# 7segement4digits1badidea-feathershield-h.net
KiCad netlist of a schematic drawn in EAGLE
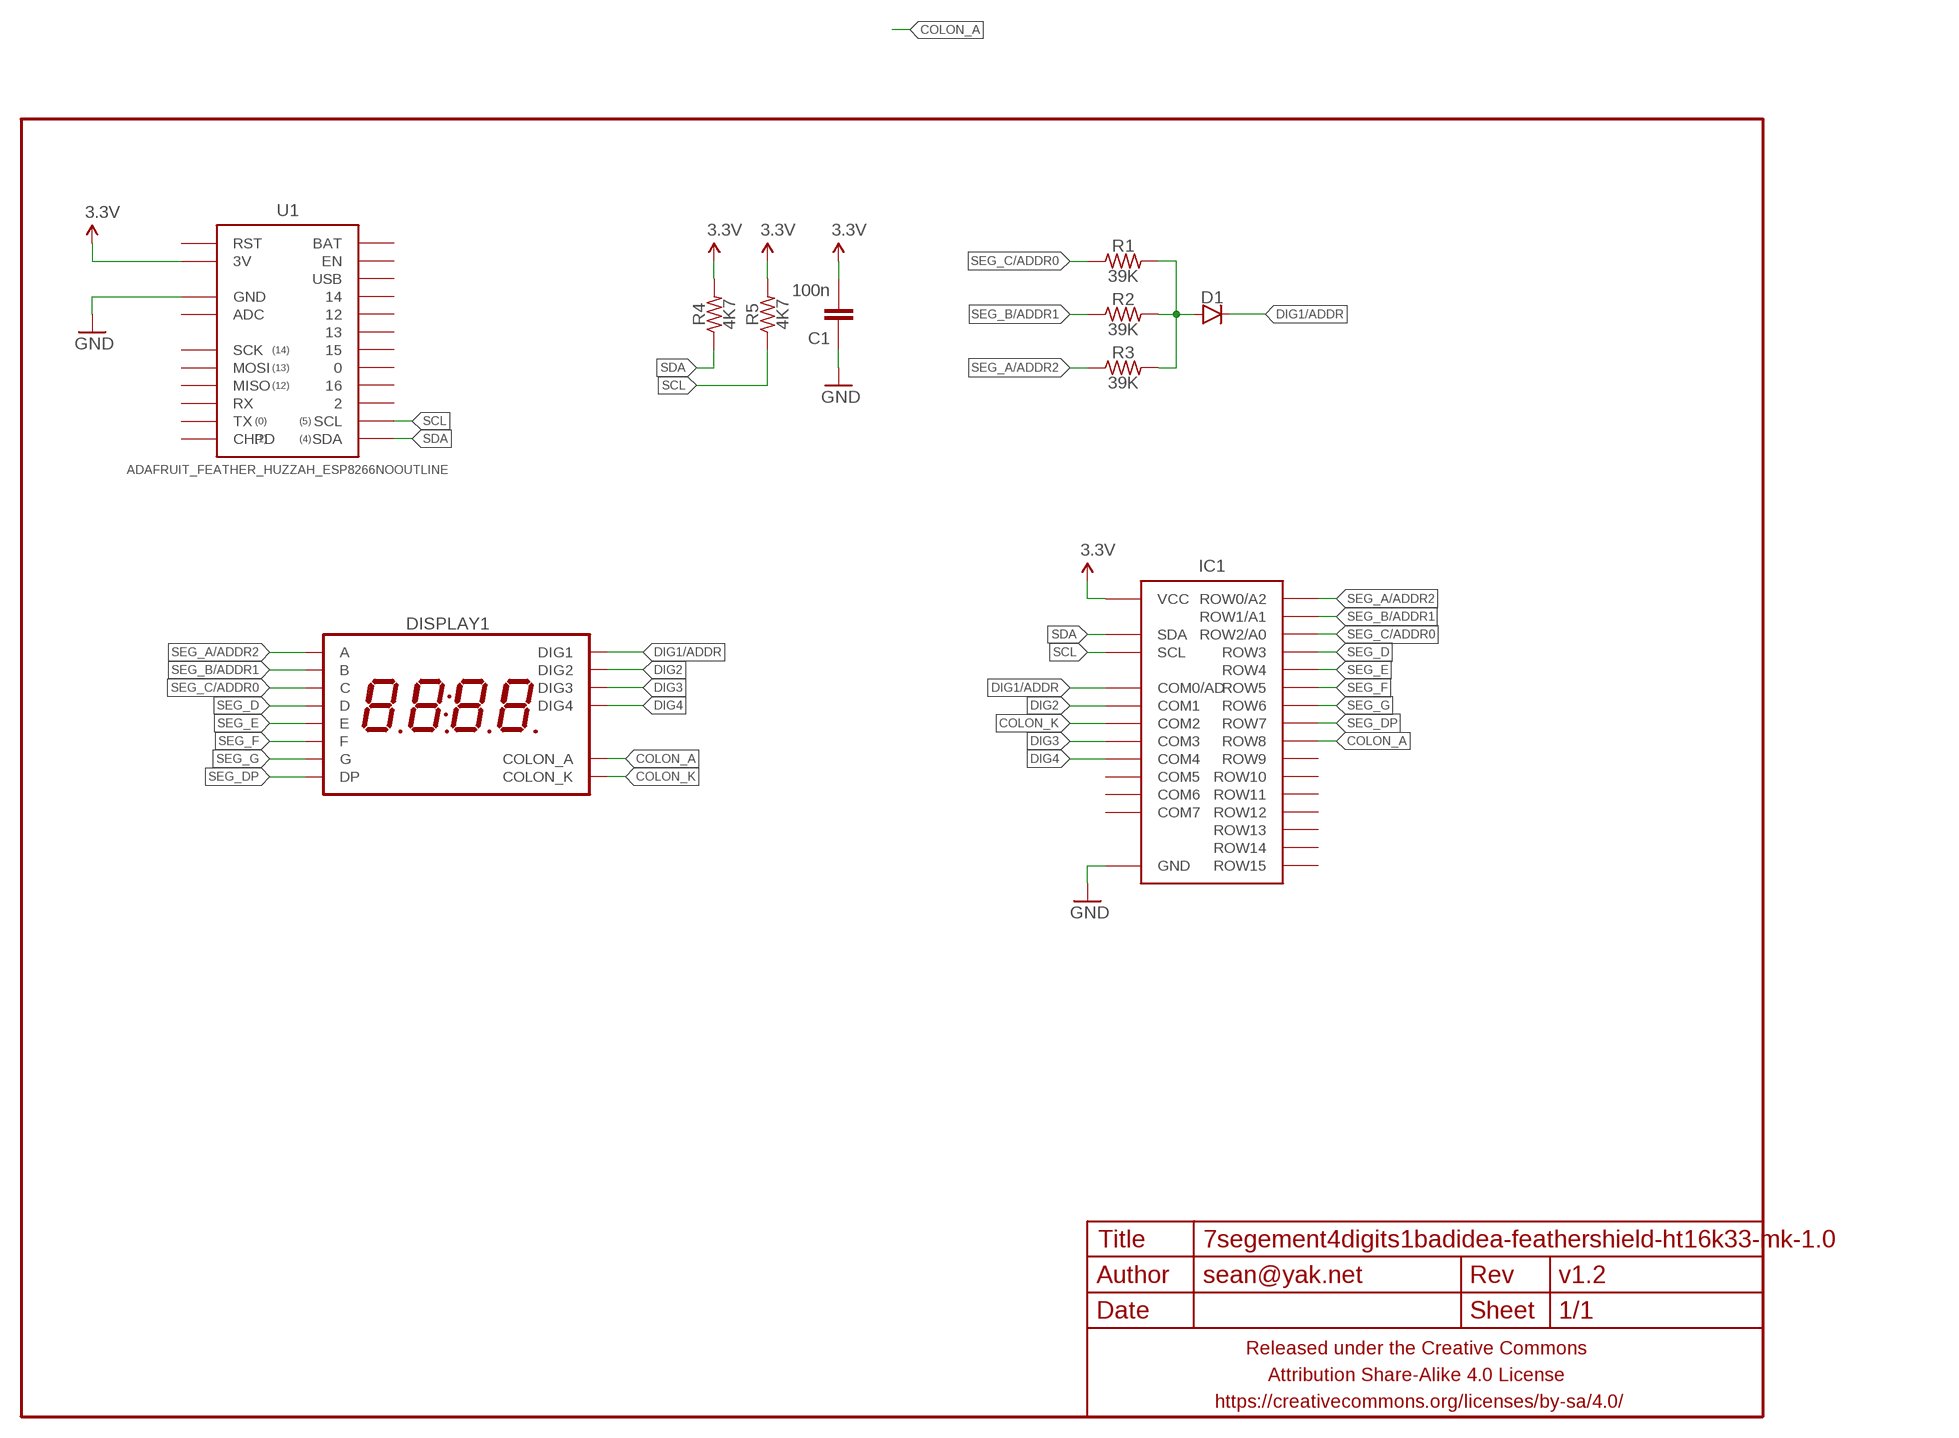
[diagram p0: schematic, sheet 1]

(export (version "E")
  (design (tool "Eeschema 10.0.6"))
  (components
    (comp (ref "C1")
      (value "100n")
      (footprint "eagle-import:C0603")
      (libsource (lib "eagle-import") (part "CAPACITOR-CERAMICC0603"))
    )
    (comp (ref "D1")
      (value "DIODESOD123")
      (footprint "eagle-import:SOD123")
      (libsource (lib "eagle-import") (part "DIODESOD123"))
    )
    (comp (ref "DISPLAY1")
      (value "7SEG_4DIGIT_COLON14.2MM-CC")
      (footprint "eagle-import:7SEG_4DIG_0.56IN_14MM_ADAFRUIT")
      (libsource (lib "eagle-import") (part "7SEG_4DIGIT_COLON14.2MM-CC"))
    )
    (comp (ref "FRAME1")
      (value "FRAME-LETTERNO_PACKAGE")
      (footprint "eagle-import:DUMMY")
      (fields (field (name "DESIGNER") "sean@yak.net") (field (name "VERSION") "v1.2"))
      (libsource (lib "eagle-import") (part "FRAME-LETTERNO_PACKAGE"))
    )
    (comp (ref "IC1")
      (value "HT16K33")
      (footprint "eagle-import:SOIC28W")
      (libsource (lib "eagle-import") (part "HT16K33-28SOIC28W"))
    )
    (comp (ref "R1")
      (value "39K")
      (footprint "eagle-import:R0603")
      (libsource (lib "eagle-import") (part "RESISTORR0603"))
    )
    (comp (ref "R2")
      (value "39K")
      (footprint "eagle-import:R0603")
      (libsource (lib "eagle-import") (part "RESISTORR0603"))
    )
    (comp (ref "R3")
      (value "39K")
      (footprint "eagle-import:R0603")
      (libsource (lib "eagle-import") (part "RESISTORR0603"))
    )
    (comp (ref "R4")
      (value "4K7")
      (footprint "eagle-import:R0603")
      (libsource (lib "eagle-import") (part "RESISTORR0603"))
    )
    (comp (ref "R5")
      (value "4K7")
      (footprint "eagle-import:R0603")
      (libsource (lib "eagle-import") (part "RESISTORR0603"))
    )
    (comp (ref "U1")
      (value "ADAFRUIT_FEATHER_HUZZAH_ESP8266NOOUTLINE")
      (footprint "eagle-import:ADAFRUIT_FEATHER_HUZZAH_NOOUTLINE")
      (libsource (lib "eagle-import") (part "ADAFRUIT_FEATHER_HUZZAH_ESP8266NOOUTLINE"))
    )
  )
  (nets
    (net (code "1") (name "3.3V") (class "Default")
      (node (ref "C1") (pin "2") (pinfunction "2_2") (pintype "passive"))
      (node (ref "IC1") (pin "28") (pinfunction "VCC_28") (pintype "bidirectional"))
      (node (ref "R4") (pin "2") (pinfunction "2_2") (pintype "passive"))
      (node (ref "R5") (pin "2") (pinfunction "2_2") (pintype "passive"))
      (node (ref "U1") (pin "3V") (pinfunction "3V_3V") (pintype "bidirectional"))
    )
    (net (code "2") (name "COLON_A") (class "Default")
      (node (ref "DISPLAY1") (pin "P$8") (pinfunction "COLON_A_P$8") (pintype "passive"))
      (node (ref "IC1") (pin "17") (pinfunction "ROW8_17") (pintype "bidirectional"))
    )
    (net (code "3") (name "COLON_K") (class "Default")
      (node (ref "DISPLAY1") (pin "P$7") (pinfunction "COLON_K_P$7") (pintype "passive"))
      (node (ref "IC1") (pin "4") (pinfunction "COM2_4") (pintype "bidirectional"))
    )
    (net (code "4") (name "DIG1{slash}ADDR") (class "Default")
      (node (ref "D1") (pin "C") (pinfunction "C_C") (pintype "passive"))
      (node (ref "DISPLAY1") (pin "P$14") (pinfunction "DIG1_P$14") (pintype "passive"))
      (node (ref "IC1") (pin "2") (pinfunction "COM0/AD_2") (pintype "bidirectional"))
    )
    (net (code "5") (name "DIG2") (class "Default")
      (node (ref "DISPLAY1") (pin "P$11") (pinfunction "DIG2_P$11") (pintype "passive"))
      (node (ref "IC1") (pin "3") (pinfunction "COM1_3") (pintype "bidirectional"))
    )
    (net (code "6") (name "DIG3") (class "Default")
      (node (ref "DISPLAY1") (pin "P$10") (pinfunction "DIG3_P$10") (pintype "passive"))
      (node (ref "IC1") (pin "5") (pinfunction "COM3_5") (pintype "bidirectional"))
    )
    (net (code "7") (name "DIG4") (class "Default")
      (node (ref "DISPLAY1") (pin "P$6") (pinfunction "DIG4_P$6") (pintype "passive"))
      (node (ref "IC1") (pin "6") (pinfunction "COM4_6") (pintype "bidirectional"))
    )
    (net (code "8") (name "GND") (class "Default")
      (node (ref "C1") (pin "1") (pinfunction "1_1") (pintype "passive"))
      (node (ref "IC1") (pin "1") (pinfunction "GND_1") (pintype "bidirectional"))
      (node (ref "U1") (pin "GND@0") (pinfunction "GND_GND@0") (pintype "bidirectional"))
    )
    (net (code "9") (name "Net-(D1-PadA)") (class "Default")
      (node (ref "D1") (pin "A") (pinfunction "A_A") (pintype "passive"))
      (node (ref "R1") (pin "2") (pinfunction "2_2") (pintype "passive"))
      (node (ref "R2") (pin "2") (pinfunction "2_2") (pintype "passive"))
      (node (ref "R3") (pin "2") (pinfunction "2_2") (pintype "passive"))
    )
    (net (code "10") (name "SCL") (class "Default")
      (node (ref "IC1") (pin "26") (pinfunction "SCL_26") (pintype "bidirectional"))
      (node (ref "R5") (pin "1") (pinfunction "1_1") (pintype "passive"))
      (node (ref "U1") (pin "SCL") (pinfunction "SCL_SCL") (pintype "bidirectional"))
    )
    (net (code "11") (name "SDA") (class "Default")
      (node (ref "IC1") (pin "27") (pinfunction "SDA_27") (pintype "bidirectional"))
      (node (ref "R4") (pin "1") (pinfunction "1_1") (pintype "passive"))
      (node (ref "U1") (pin "SDA") (pinfunction "SDA_SDA") (pintype "bidirectional"))
    )
    (net (code "12") (name "SEG_A{slash}ADDR2") (class "Default")
      (node (ref "DISPLAY1") (pin "P$13") (pinfunction "A_P$13") (pintype "passive"))
      (node (ref "IC1") (pin "25") (pinfunction "ROW0/A2_25") (pintype "bidirectional"))
      (node (ref "R3") (pin "1") (pinfunction "1_1") (pintype "passive"))
    )
    (net (code "13") (name "SEG_B{slash}ADDR1") (class "Default")
      (node (ref "DISPLAY1") (pin "P$9") (pinfunction "B_P$9") (pintype "passive"))
      (node (ref "IC1") (pin "24") (pinfunction "ROW1/A1_24") (pintype "bidirectional"))
      (node (ref "R2") (pin "1") (pinfunction "1_1") (pintype "passive"))
    )
    (net (code "14") (name "SEG_C{slash}ADDR0") (class "Default")
      (node (ref "DISPLAY1") (pin "P$4") (pinfunction "C_P$4") (pintype "passive"))
      (node (ref "IC1") (pin "23") (pinfunction "ROW2/A0_23") (pintype "bidirectional"))
      (node (ref "R1") (pin "1") (pinfunction "1_1") (pintype "passive"))
    )
    (net (code "15") (name "SEG_D") (class "Default")
      (node (ref "DISPLAY1") (pin "P$2") (pinfunction "D_P$2") (pintype "passive"))
      (node (ref "IC1") (pin "22") (pinfunction "ROW3_22") (pintype "bidirectional"))
    )
    (net (code "16") (name "SEG_DP") (class "Default")
      (node (ref "DISPLAY1") (pin "P$3") (pinfunction "DP_P$3") (pintype "passive"))
      (node (ref "IC1") (pin "18") (pinfunction "ROW7_18") (pintype "bidirectional"))
    )
    (net (code "17") (name "SEG_E") (class "Default")
      (node (ref "DISPLAY1") (pin "P$1") (pinfunction "E_P$1") (pintype "passive"))
      (node (ref "IC1") (pin "21") (pinfunction "ROW4_21") (pintype "bidirectional"))
    )
    (net (code "18") (name "SEG_F") (class "Default")
      (node (ref "DISPLAY1") (pin "P$12") (pinfunction "F_P$12") (pintype "passive"))
      (node (ref "IC1") (pin "20") (pinfunction "ROW5_20") (pintype "bidirectional"))
    )
    (net (code "19") (name "SEG_G") (class "Default")
      (node (ref "DISPLAY1") (pin "P$5") (pinfunction "G_P$5") (pintype "passive"))
      (node (ref "IC1") (pin "19") (pinfunction "ROW6_19") (pintype "bidirectional"))
    )
    (net (code "20") (name "unconnected-(IC1-COM5-Pad7)") (class "Default")
      (node (ref "IC1") (pin "7") (pinfunction "COM5_7") (pintype "bidirectional"))
    )
    (net (code "21") (name "unconnected-(IC1-COM6-Pad8)") (class "Default")
      (node (ref "IC1") (pin "8") (pinfunction "COM6_8") (pintype "bidirectional"))
    )
    (net (code "22") (name "unconnected-(IC1-COM7-Pad9)") (class "Default")
      (node (ref "IC1") (pin "9") (pinfunction "COM7_9") (pintype "bidirectional"))
    )
    (net (code "23") (name "unconnected-(IC1-ROW9-Pad16)") (class "Default")
      (node (ref "IC1") (pin "16") (pinfunction "ROW9_16") (pintype "bidirectional"))
    )
    (net (code "24") (name "unconnected-(IC1-ROW10-Pad15)") (class "Default")
      (node (ref "IC1") (pin "15") (pinfunction "ROW10_15") (pintype "bidirectional"))
    )
    (net (code "25") (name "unconnected-(IC1-ROW11-Pad14)") (class "Default")
      (node (ref "IC1") (pin "14") (pinfunction "ROW11_14") (pintype "bidirectional"))
    )
    (net (code "26") (name "unconnected-(IC1-ROW12-Pad13)") (class "Default")
      (node (ref "IC1") (pin "13") (pinfunction "ROW12_13") (pintype "bidirectional"))
    )
    (net (code "27") (name "unconnected-(IC1-ROW13-Pad12)") (class "Default")
      (node (ref "IC1") (pin "12") (pinfunction "ROW13_12") (pintype "bidirectional"))
    )
    (net (code "28") (name "unconnected-(IC1-ROW14-Pad11)") (class "Default")
      (node (ref "IC1") (pin "11") (pinfunction "ROW14_11") (pintype "bidirectional"))
    )
    (net (code "29") (name "unconnected-(IC1-ROW15-Pad10)") (class "Default")
      (node (ref "IC1") (pin "10") (pinfunction "ROW15_10") (pintype "bidirectional"))
    )
    (net (code "30") (name "unconnected-(U1-Pad0)") (class "Default")
      (node (ref "U1") (pin "0") (pinfunction "0_0") (pintype "bidirectional"))
    )
    (net (code "31") (name "unconnected-(U1-Pad2)") (class "Default")
      (node (ref "U1") (pin "2") (pinfunction "2_2") (pintype "bidirectional"))
    )
    (net (code "32") (name "unconnected-(U1-Pad12)") (class "Default")
      (node (ref "U1") (pin "12") (pinfunction "12_12") (pintype "bidirectional"))
    )
    (net (code "33") (name "unconnected-(U1-Pad13)") (class "Default")
      (node (ref "U1") (pin "13") (pinfunction "13_13") (pintype "bidirectional"))
    )
    (net (code "34") (name "unconnected-(U1-Pad14)") (class "Default")
      (node (ref "U1") (pin "14") (pinfunction "14_14") (pintype "bidirectional"))
    )
    (net (code "35") (name "unconnected-(U1-Pad15)") (class "Default")
      (node (ref "U1") (pin "15") (pinfunction "15_15") (pintype "bidirectional"))
    )
    (net (code "36") (name "unconnected-(U1-Pad16)") (class "Default")
      (node (ref "U1") (pin "16") (pinfunction "16_16") (pintype "bidirectional"))
    )
    (net (code "37") (name "unconnected-(U1-PadADC)") (class "Default")
      (node (ref "U1") (pin "ADC") (pinfunction "ADC_ADC") (pintype "bidirectional"))
    )
    (net (code "38") (name "unconnected-(U1-PadBAT)") (class "Default")
      (node (ref "U1") (pin "BAT") (pinfunction "BAT_BAT") (pintype "bidirectional"))
    )
    (net (code "39") (name "unconnected-(U1-PadCHPD)") (class "Default")
      (node (ref "U1") (pin "CHPD") (pinfunction "CHPD_CHPD") (pintype "bidirectional"))
    )
    (net (code "40") (name "unconnected-(U1-PadEN)") (class "Default")
      (node (ref "U1") (pin "EN") (pinfunction "EN_EN") (pintype "bidirectional"))
    )
    (net (code "41") (name "unconnected-(U1-PadMISO)") (class "Default")
      (node (ref "U1") (pin "MISO") (pinfunction "MISO_MISO") (pintype "bidirectional"))
    )
    (net (code "42") (name "unconnected-(U1-PadMOSI)") (class "Default")
      (node (ref "U1") (pin "MOSI") (pinfunction "MOSI_MOSI") (pintype "bidirectional"))
    )
    (net (code "43") (name "unconnected-(U1-PadRST)") (class "Default")
      (node (ref "U1") (pin "RST") (pinfunction "RST_RST") (pintype "bidirectional"))
    )
    (net (code "44") (name "unconnected-(U1-PadRX)") (class "Default")
      (node (ref "U1") (pin "RX") (pinfunction "RX_RX") (pintype "bidirectional"))
    )
    (net (code "45") (name "unconnected-(U1-PadSCK)") (class "Default")
      (node (ref "U1") (pin "SCK") (pinfunction "SCK_SCK") (pintype "bidirectional"))
    )
    (net (code "46") (name "unconnected-(U1-PadTX)") (class "Default")
      (node (ref "U1") (pin "TX") (pinfunction "TX_TX") (pintype "bidirectional"))
    )
    (net (code "47") (name "unconnected-(U1-PadUSB)") (class "Default")
      (node (ref "U1") (pin "USB") (pinfunction "USB_USB") (pintype "bidirectional"))
    )
  )
)
